# BlueDaq_V1_0.net
KiCad netlist of a schematic drawn in EAGLE
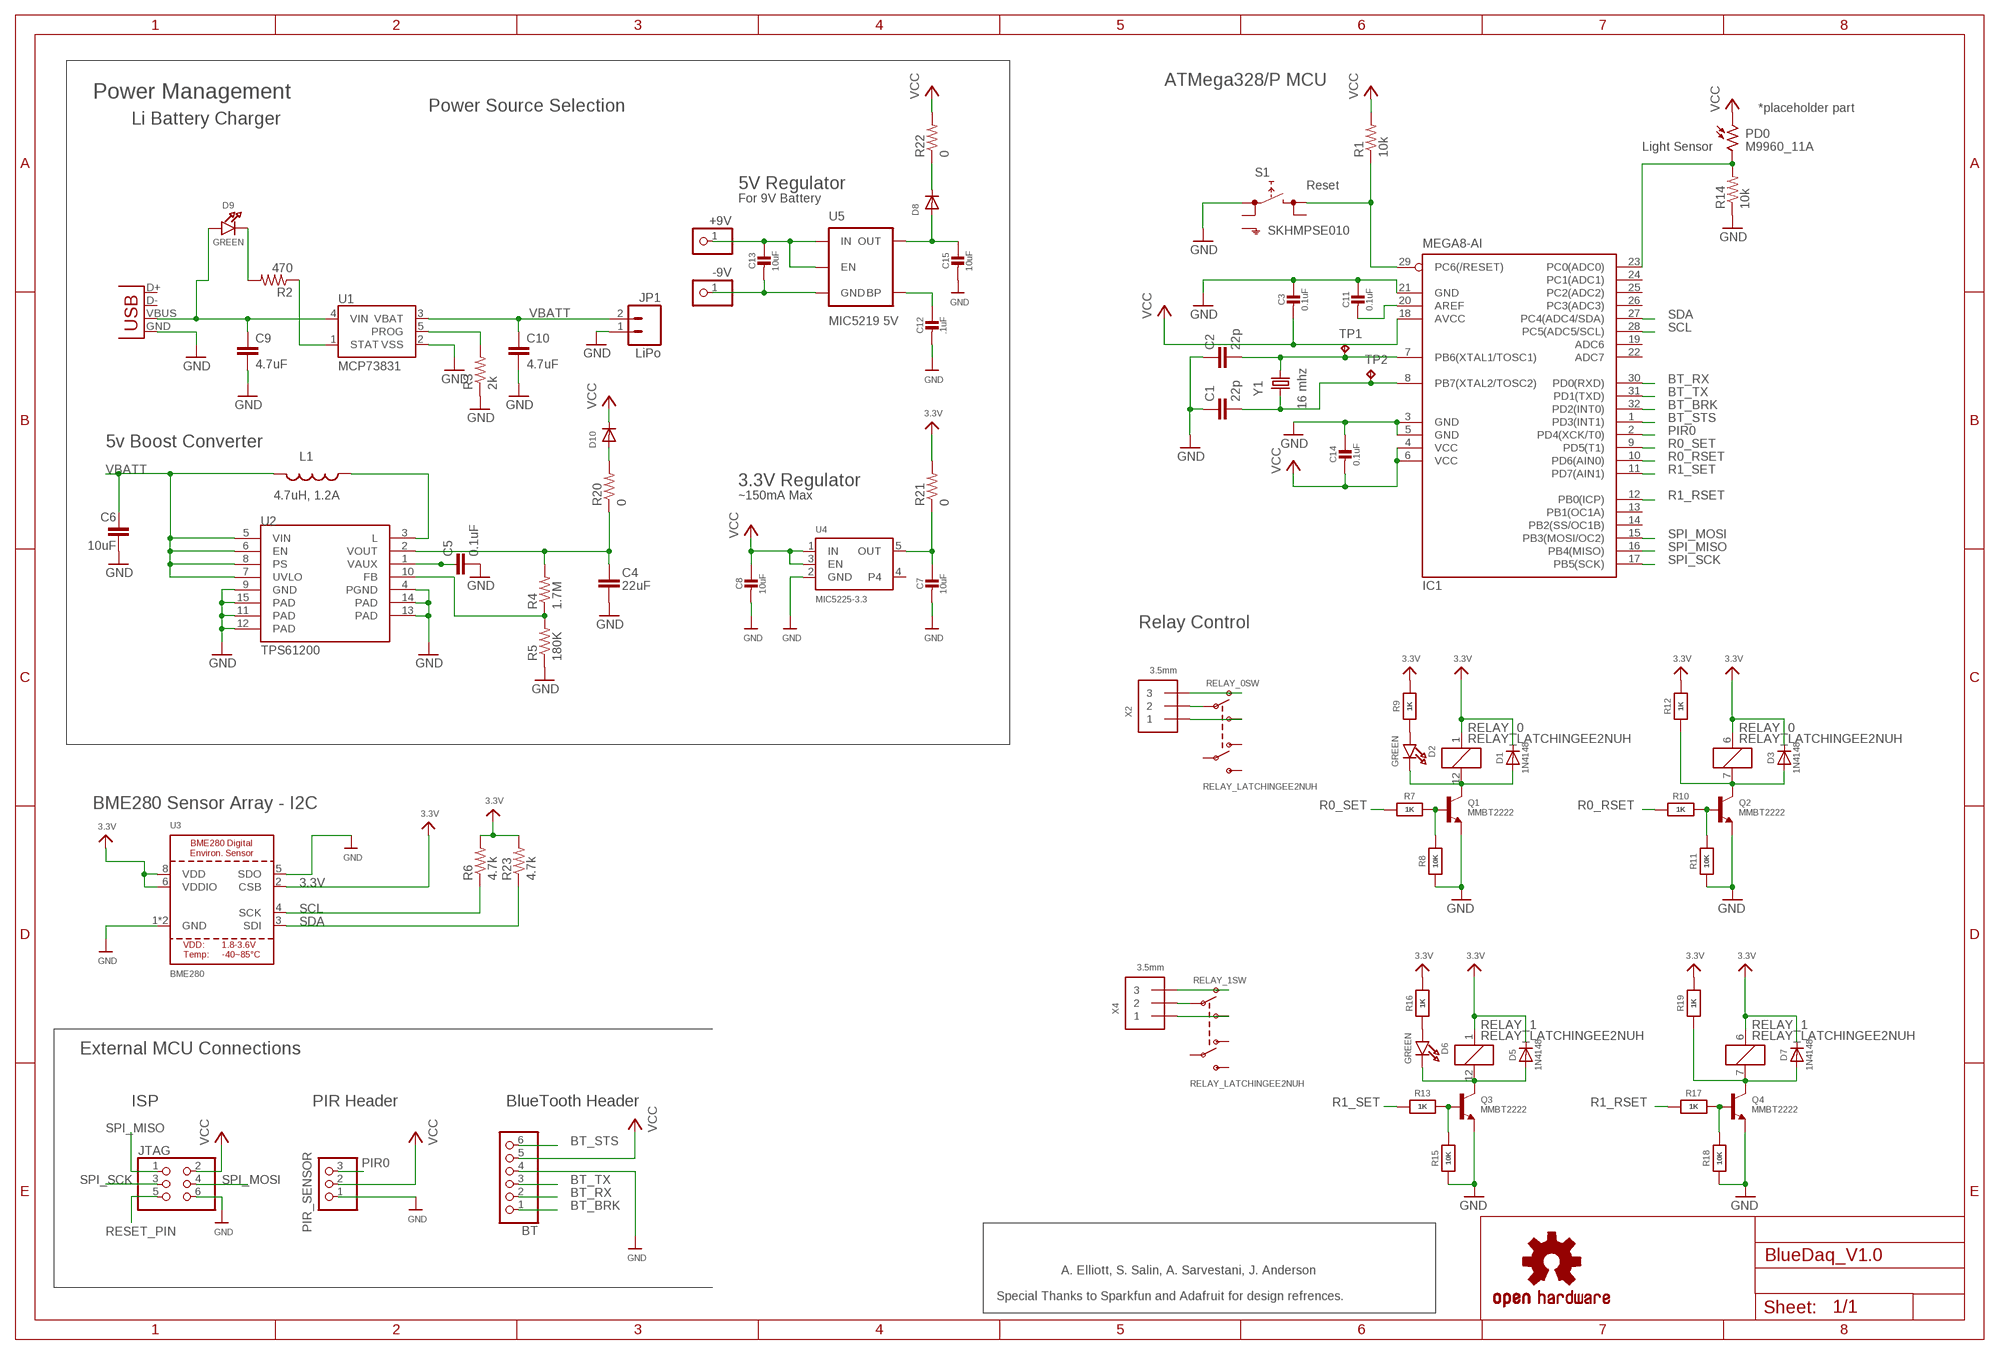
[diagram p0: schematic, sheet 1]

(export (version "E")
  (design (tool "Eeschema 10.0.6"))
  (components
    (comp (ref "+9V")
      (value "PINHD-1X1")
      (footprint "eagle-import:1X01")
      (libsource (lib "eagle-import") (part "PINHD-1X1"))
    )
    (comp (ref "-9V")
      (value "PINHD-1X1")
      (footprint "eagle-import:1X01")
      (libsource (lib "eagle-import") (part "PINHD-1X1"))
    )
    (comp (ref "BT")
      (value "PINHD-1X6")
      (footprint "eagle-import:1X06")
      (libsource (lib "eagle-import") (part "PINHD-1X6"))
    )
    (comp (ref "C1")
      (value "22p")
      (footprint "eagle-import:C0805")
      (libsource (lib "eagle-import") (part "C-EUC0805"))
    )
    (comp (ref "C2")
      (value "22p")
      (footprint "eagle-import:C0805")
      (libsource (lib "eagle-import") (part "C-EUC0805"))
    )
    (comp (ref "C3")
      (value "0.1uF")
      (footprint "eagle-import:0805-NO@1")
      (libsource (lib "eagle-import") (part "CAP_CERAMIC0805-NOOUTLINE"))
    )
    (comp (ref "C4")
      (value "22uF")
      (footprint "eagle-import:0805")
      (libsource (lib "eagle-import") (part "CAP0805"))
    )
    (comp (ref "C5")
      (value "0.1uF")
      (footprint "eagle-import:0805")
      (libsource (lib "eagle-import") (part "SparkFun_CAP0805"))
    )
    (comp (ref "C6")
      (value "10uF")
      (footprint "eagle-import:1206")
      (libsource (lib "eagle-import") (part "CAP1206"))
    )
    (comp (ref "C7")
      (value "10uF")
      (footprint "eagle-import:0805-NO@1")
      (libsource (lib "eagle-import") (part "CAP_CERAMIC0805-NOOUTLINE"))
    )
    (comp (ref "C8")
      (value "10uF")
      (footprint "eagle-import:0805-NO@1")
      (libsource (lib "eagle-import") (part "CAP_CERAMIC0805-NOOUTLINE"))
    )
    (comp (ref "C9")
      (value "4.7uF")
      (footprint "eagle-import:0805")
      (libsource (lib "eagle-import") (part "SparkFun_CAP0805"))
    )
    (comp (ref "C10")
      (value "4.7uF")
      (footprint "eagle-import:0805")
      (libsource (lib "eagle-import") (part "SparkFun_CAP0805"))
    )
    (comp (ref "C11")
      (value "0.1uF")
      (footprint "eagle-import:0805-NO@1")
      (libsource (lib "eagle-import") (part "CAP_CERAMIC0805-NOOUTLINE"))
    )
    (comp (ref "C12")
      (value ".1uF")
      (footprint "eagle-import:0805-NO@1")
      (libsource (lib "eagle-import") (part "CAP_CERAMIC0805-NOOUTLINE"))
    )
    (comp (ref "C13")
      (value "10uF")
      (footprint "eagle-import:0805-NO@1")
      (libsource (lib "eagle-import") (part "CAP_CERAMIC0805-NOOUTLINE"))
    )
    (comp (ref "C14")
      (value "0.1uF")
      (footprint "eagle-import:0805-NO@1")
      (libsource (lib "eagle-import") (part "CAP_CERAMIC0805-NOOUTLINE"))
    )
    (comp (ref "C15")
      (value "10uF")
      (footprint "eagle-import:0805-NO@1")
      (libsource (lib "eagle-import") (part "CAP_CERAMIC0805-NOOUTLINE"))
    )
    (comp (ref "D1")
      (value "1N4148")
      (footprint "eagle-import:SOD-323")
      (libsource (lib "eagle-import") (part "DIODESOD-323"))
    )
    (comp (ref "D2")
      (value "GREEN")
      (footprint "eagle-import:CHIPLED_0805_NOOUTLINE")
      (libsource (lib "eagle-import") (part "LED0805_NOOUTLINE"))
    )
    (comp (ref "D3")
      (value "1N4148")
      (footprint "eagle-import:SOD-323")
      (libsource (lib "eagle-import") (part "DIODESOD-323"))
    )
    (comp (ref "D5")
      (value "1N4148")
      (footprint "eagle-import:SOD-323")
      (libsource (lib "eagle-import") (part "DIODESOD-323"))
    )
    (comp (ref "D6")
      (value "GREEN")
      (footprint "eagle-import:CHIPLED_0805_NOOUTLINE")
      (libsource (lib "eagle-import") (part "LED0805_NOOUTLINE"))
    )
    (comp (ref "D7")
      (value "1N4148")
      (footprint "eagle-import:SOD-323")
      (libsource (lib "eagle-import") (part "DIODESOD-323"))
    )
    (comp (ref "D8")
      (value "DIODESMA")
      (footprint "eagle-import:SMADIODE")
      (libsource (lib "eagle-import") (part "DIODESMA"))
    )
    (comp (ref "D9")
      (value "GREEN")
      (footprint "eagle-import:CHIPLED_0805_NOOUTLINE")
      (libsource (lib "eagle-import") (part "LED0805_NOOUTLINE"))
    )
    (comp (ref "D10")
      (value "DIODESMA")
      (footprint "eagle-import:SMADIODE")
      (libsource (lib "eagle-import") (part "DIODESMA"))
    )
    (comp (ref "IC1")
      (value "MEGA8-AI")
      (footprint "eagle-import:TQFP32-08")
      (fields (field (name "MPN") "ATMEGA8-16AU"))
      (libsource (lib "eagle-import") (part "MEGA8-AI"))
    )
    (comp (ref "JP1")
      (value "LiPo")
      (footprint "eagle-import:JST-2-SMD")
      (libsource (lib "eagle-import") (part "M02-JST-2MM-SMT"))
    )
    (comp (ref "JTAG")
      (value "PINHD-2X3")
      (footprint "eagle-import:2X03")
      (libsource (lib "eagle-import") (part "PINHD-2X3"))
    )
    (comp (ref "L1")
      (value "4.7uH, 1.2A")
      (footprint "eagle-import:CDRH2D09")
      (libsource (lib "eagle-import") (part "INDUCTOR."))
    )
    (comp (ref "PD0")
      (value "M9960_11A")
      (footprint "eagle-import:M9960")
      (libsource (lib "eagle-import") (part "M9960_11A"))
    )
    (comp (ref "PIR_SENSOR")
      (value "PINHD-1X3")
      (footprint "eagle-import:1X03")
      (libsource (lib "eagle-import") (part "PINHD-1X3"))
    )
    (comp (ref "Q1")
      (value "MMBT2222")
      (footprint "eagle-import:SOT23-R")
      (libsource (lib "eagle-import") (part "TRANSISTOR_NPN"))
    )
    (comp (ref "Q2")
      (value "MMBT2222")
      (footprint "eagle-import:SOT23-R")
      (libsource (lib "eagle-import") (part "TRANSISTOR_NPN"))
    )
    (comp (ref "Q3")
      (value "MMBT2222")
      (footprint "eagle-import:SOT23-R")
      (libsource (lib "eagle-import") (part "TRANSISTOR_NPN"))
    )
    (comp (ref "Q4")
      (value "MMBT2222")
      (footprint "eagle-import:SOT23-R")
      (libsource (lib "eagle-import") (part "TRANSISTOR_NPN"))
    )
    (comp (ref "R1")
      (value "10k")
      (footprint "eagle-import:R0805")
      (libsource (lib "eagle-import") (part "R-US_R0805"))
    )
    (comp (ref "R2")
      (value "470")
      (footprint "eagle-import:R0805")
      (libsource (lib "eagle-import") (part "R-US_R0805"))
    )
    (comp (ref "R3")
      (value "2k")
      (footprint "eagle-import:R0805")
      (libsource (lib "eagle-import") (part "R-US_R0805"))
    )
    (comp (ref "R4")
      (value "1.7M")
      (footprint "eagle-import:R0805")
      (libsource (lib "eagle-import") (part "R-US_R0805"))
    )
    (comp (ref "R5")
      (value "180K")
      (footprint "eagle-import:R0805")
      (libsource (lib "eagle-import") (part "R-US_R0805"))
    )
    (comp (ref "R6")
      (value "4.7k")
      (footprint "eagle-import:R0805")
      (libsource (lib "eagle-import") (part "R-US_R0805"))
    )
    (comp (ref "R7")
      (value "1K")
      (footprint "eagle-import:0805-NO")
      (libsource (lib "eagle-import") (part "RESISTOR0805_NOOUTLINE"))
    )
    (comp (ref "R8")
      (value "10K")
      (footprint "eagle-import:0805-NO")
      (libsource (lib "eagle-import") (part "RESISTOR0805_NOOUTLINE"))
    )
    (comp (ref "R9")
      (value "1K")
      (footprint "eagle-import:0805-NO")
      (libsource (lib "eagle-import") (part "RESISTOR0805_NOOUTLINE"))
    )
    (comp (ref "R10")
      (value "1K")
      (footprint "eagle-import:0805-NO")
      (libsource (lib "eagle-import") (part "RESISTOR0805_NOOUTLINE"))
    )
    (comp (ref "R11")
      (value "10K")
      (footprint "eagle-import:0805-NO")
      (libsource (lib "eagle-import") (part "RESISTOR0805_NOOUTLINE"))
    )
    (comp (ref "R12")
      (value "1K")
      (footprint "eagle-import:0805-NO")
      (libsource (lib "eagle-import") (part "RESISTOR0805_NOOUTLINE"))
    )
    (comp (ref "R13")
      (value "1K")
      (footprint "eagle-import:0805-NO")
      (libsource (lib "eagle-import") (part "RESISTOR0805_NOOUTLINE"))
    )
    (comp (ref "R14")
      (value "10k")
      (footprint "eagle-import:R0805")
      (libsource (lib "eagle-import") (part "R-US_R0805"))
    )
    (comp (ref "R15")
      (value "10K")
      (footprint "eagle-import:0805-NO")
      (libsource (lib "eagle-import") (part "RESISTOR0805_NOOUTLINE"))
    )
    (comp (ref "R16")
      (value "1K")
      (footprint "eagle-import:0805-NO")
      (libsource (lib "eagle-import") (part "RESISTOR0805_NOOUTLINE"))
    )
    (comp (ref "R17")
      (value "1K")
      (footprint "eagle-import:0805-NO")
      (libsource (lib "eagle-import") (part "RESISTOR0805_NOOUTLINE"))
    )
    (comp (ref "R18")
      (value "10K")
      (footprint "eagle-import:0805-NO")
      (libsource (lib "eagle-import") (part "RESISTOR0805_NOOUTLINE"))
    )
    (comp (ref "R19")
      (value "1K")
      (footprint "eagle-import:0805-NO")
      (libsource (lib "eagle-import") (part "RESISTOR0805_NOOUTLINE"))
    )
    (comp (ref "R20")
      (value "0")
      (footprint "eagle-import:R0805")
      (libsource (lib "eagle-import") (part "R-US_R0805"))
    )
    (comp (ref "R21")
      (value "0")
      (footprint "eagle-import:R0805")
      (libsource (lib "eagle-import") (part "R-US_R0805"))
    )
    (comp (ref "R22")
      (value "0")
      (footprint "eagle-import:R0805")
      (libsource (lib "eagle-import") (part "R-US_R0805"))
    )
    (comp (ref "R23")
      (value "4.7k")
      (footprint "eagle-import:R0805")
      (libsource (lib "eagle-import") (part "R-US_R0805"))
    )
    (comp (ref "RELAY_0")
      (value "RELAY_LATCHINGEE2NUH")
      (footprint "eagle-import:RELAY_EE2_LATCH")
      (libsource (lib "eagle-import") (part "RELAY_LATCHINGEE2NUH"))
    )
    (comp (ref "RELAY_1")
      (value "RELAY_LATCHINGEE2NUH")
      (footprint "eagle-import:RELAY_EE2_LATCH")
      (libsource (lib "eagle-import") (part "RELAY_LATCHINGEE2NUH"))
    )
    (comp (ref "S1")
      (value "SKHMPSE010")
      (footprint "eagle-import:SKHMPXE010")
      (libsource (lib "eagle-import") (part "SKHMPE010S"))
    )
    (comp (ref "TP1")
      (value "TPTP19SQ")
      (footprint "eagle-import:TP19SQ")
      (libsource (lib "eagle-import") (part "TPTP19SQ"))
    )
    (comp (ref "TP2")
      (value "TPTP19SQ")
      (footprint "eagle-import:TP19SQ")
      (libsource (lib "eagle-import") (part "TPTP19SQ"))
    )
    (comp (ref "U$22")
      (value "OSHW-LOGOS")
      (footprint "eagle-import:OSHW-LOGO-S")
      (libsource (lib "eagle-import") (part "OSHW-LOGOS"))
    )
    (comp (ref "U1")
      (value "MCP73831")
      (footprint "eagle-import:SOT23-5")
      (libsource (lib "eagle-import") (part "MCP73831"))
    )
    (comp (ref "U2")
      (value "TPS61200")
      (footprint "eagle-import:QFN-10_PAD")
      (libsource (lib "eagle-import") (part "TPS61200"))
    )
    (comp (ref "U3")
      (value "BME280")
      (footprint "eagle-import:BME280")
      (libsource (lib "eagle-import") (part "BME280"))
    )
    (comp (ref "U4")
      (value "MIC5225-3.3")
      (footprint "eagle-import:SOT23-5")
      (libsource (lib "eagle-import") (part "VREG_SOT23-5"))
    )
    (comp (ref "U5")
      (value "MIC5219 5V")
      (footprint "eagle-import:SOT23-5")
      (libsource (lib "eagle-import") (part "V_REG_MIC52195V"))
    )
    (comp (ref "X1")
      (value "USB-MICROB")
      (footprint "eagle-import:USB-MICROB")
      (libsource (lib "eagle-import") (part "USB-MICROB"))
    )
    (comp (ref "X2")
      (value "3.5mm")
      (footprint "eagle-import:TERMBLOCK_1X3-3.5MM")
      (libsource (lib "eagle-import") (part "TERMBLOCK_1X3"))
    )
    (comp (ref "X4")
      (value "3.5mm")
      (footprint "eagle-import:TERMBLOCK_1X3-3.5MM")
      (libsource (lib "eagle-import") (part "TERMBLOCK_1X3"))
    )
    (comp (ref "Y1")
      (value "16 mhz")
      (footprint "eagle-import:HC49U-V")
      (libsource (lib "eagle-import") (part "CRYSTALHC49UV"))
    )
  )
  (nets
    (net (code "1") (name "/BT_BRK") (class "Default")
      (node (ref "BT") (pin "1") (pinfunction "1_1") (pintype "passive"))
      (node (ref "IC1") (pin "32") (pinfunction "PD2(INT0)_32") (pintype "bidirectional"))
    )
    (net (code "2") (name "/BT_RX") (class "Default")
      (node (ref "BT") (pin "2") (pinfunction "2_2") (pintype "passive"))
      (node (ref "IC1") (pin "30") (pinfunction "PD0(RXD)_30") (pintype "bidirectional"))
    )
    (net (code "3") (name "/BT_STS") (class "Default")
      (node (ref "BT") (pin "6") (pinfunction "6_6") (pintype "passive"))
      (node (ref "IC1") (pin "1") (pinfunction "PD3(INT1)_1") (pintype "bidirectional"))
    )
    (net (code "4") (name "/BT_TX") (class "Default")
      (node (ref "BT") (pin "3") (pinfunction "3_3") (pintype "passive"))
      (node (ref "IC1") (pin "31") (pinfunction "PD1(TXD)_31") (pintype "bidirectional"))
    )
    (net (code "5") (name "/PIR0") (class "Default")
      (node (ref "IC1") (pin "2") (pinfunction "PD4(XCK/T0)_2") (pintype "bidirectional"))
      (node (ref "PIR_SENSOR") (pin "3") (pinfunction "3_3") (pintype "passive"))
    )
    (net (code "6") (name "/R0_RSET") (class "Default")
      (node (ref "IC1") (pin "10") (pinfunction "PD6(AIN0)_10") (pintype "bidirectional"))
      (node (ref "R10") (pin "1") (pinfunction "1_1") (pintype "passive"))
    )
    (net (code "7") (name "/R0_SET") (class "Default")
      (node (ref "IC1") (pin "9") (pinfunction "PD5(T1)_9") (pintype "bidirectional"))
      (node (ref "R7") (pin "1") (pinfunction "1_1") (pintype "passive"))
    )
    (net (code "8") (name "/R1_RSET") (class "Default")
      (node (ref "IC1") (pin "12") (pinfunction "PB0(ICP)_12") (pintype "bidirectional"))
      (node (ref "R17") (pin "1") (pinfunction "1_1") (pintype "passive"))
    )
    (net (code "9") (name "/R1_SET") (class "Default")
      (node (ref "IC1") (pin "11") (pinfunction "PD7(AIN1)_11") (pintype "bidirectional"))
      (node (ref "R13") (pin "1") (pinfunction "1_1") (pintype "passive"))
    )
    (net (code "10") (name "/RESET_PIN") (class "Default")
      (node (ref "IC1") (pin "29") (pinfunction "PC6(/RESET)_29") (pintype "bidirectional"))
      (node (ref "JTAG") (pin "5") (pinfunction "5_5") (pintype "passive"))
      (node (ref "R1") (pin "1") (pinfunction "1_1") (pintype "passive"))
      (node (ref "S1") (pin "3") (pinfunction "2.1_3") (pintype "passive"))
    )
    (net (code "11") (name "/SCL") (class "Default")
      (node (ref "IC1") (pin "28") (pinfunction "PC5(ADC5/SCL)_28") (pintype "bidirectional"))
      (node (ref "R6") (pin "1") (pinfunction "1_1") (pintype "passive"))
      (node (ref "U3") (pin "4") (pinfunction "SCK_4") (pintype "input"))
    )
    (net (code "12") (name "/SDA") (class "Default")
      (node (ref "IC1") (pin "27") (pinfunction "PC4(ADC4/SDA)_27") (pintype "bidirectional"))
      (node (ref "R23") (pin "1") (pinfunction "1_1") (pintype "passive"))
      (node (ref "U3") (pin "3") (pinfunction "SDI_3") (pintype "input"))
    )
    (net (code "13") (name "/SPI_MISO") (class "Default")
      (node (ref "IC1") (pin "16") (pinfunction "PB4(MISO)_16") (pintype "bidirectional"))
      (node (ref "JTAG") (pin "1") (pinfunction "1_1") (pintype "passive"))
    )
    (net (code "14") (name "/SPI_MOSI") (class "Default")
      (node (ref "IC1") (pin "15") (pinfunction "PB3(MOSI/OC2)_15") (pintype "bidirectional"))
      (node (ref "JTAG") (pin "4") (pinfunction "4_4") (pintype "passive"))
    )
    (net (code "15") (name "/SPI_SCK") (class "Default")
      (node (ref "IC1") (pin "17") (pinfunction "PB5(SCK)_17") (pintype "bidirectional"))
      (node (ref "JTAG") (pin "3") (pinfunction "3_3") (pintype "passive"))
    )
    (net (code "16") (name "/VBATT") (class "Default")
      (node (ref "C10") (pin "1") (pinfunction "1_1") (pintype "passive"))
      (node (ref "C6") (pin "1") (pinfunction "1_1") (pintype "passive"))
      (node (ref "JP1") (pin "2") (pinfunction "2_2") (pintype "passive"))
      (node (ref "L1") (pin "P$2") (pinfunction "2_P$2") (pintype "passive"))
      (node (ref "U1") (pin "3") (pinfunction "VBAT_3") (pintype "power_in"))
      (node (ref "U2") (pin "5") (pinfunction "VIN_5") (pintype "power_in"))
      (node (ref "U2") (pin "6") (pinfunction "EN_6") (pintype "input"))
      (node (ref "U2") (pin "7") (pinfunction "UVLO_7") (pintype "passive"))
      (node (ref "U2") (pin "8") (pinfunction "PS_8") (pintype "input"))
    )
    (net (code "17") (name "3.3V") (class "Default")
      (node (ref "D1") (pin "C") (pinfunction "C_C") (pintype "passive"))
      (node (ref "D3") (pin "C") (pinfunction "C_C") (pintype "passive"))
      (node (ref "D5") (pin "C") (pinfunction "C_C") (pintype "passive"))
      (node (ref "D7") (pin "C") (pinfunction "C_C") (pintype "passive"))
      (node (ref "R12") (pin "2") (pinfunction "2_2") (pintype "passive"))
      (node (ref "R16") (pin "2") (pinfunction "2_2") (pintype "passive"))
      (node (ref "R19") (pin "2") (pinfunction "2_2") (pintype "passive"))
      (node (ref "R21") (pin "2") (pinfunction "2_2") (pintype "passive"))
      (node (ref "R23") (pin "2") (pinfunction "2_2") (pintype "passive"))
      (node (ref "R6") (pin "2") (pinfunction "2_2") (pintype "passive"))
      (node (ref "R9") (pin "2") (pinfunction "2_2") (pintype "passive"))
      (node (ref "RELAY_0") (pin "1") (pinfunction "1_1") (pintype "passive"))
      (node (ref "RELAY_0") (pin "6") (pinfunction "1_6") (pintype "passive"))
      (node (ref "RELAY_1") (pin "1") (pinfunction "1_1") (pintype "passive"))
      (node (ref "RELAY_1") (pin "6") (pinfunction "1_6") (pintype "passive"))
      (node (ref "U3") (pin "2") (pinfunction "CSB_2") (pintype "input"))
      (node (ref "U3") (pin "6") (pinfunction "VDDIO_6") (pintype "power_in"))
      (node (ref "U3") (pin "8") (pinfunction "VDD_8") (pintype "power_in"))
    )
    (net (code "18") (name "GND") (class "Default")
      (node (ref "BT") (pin "4") (pinfunction "4_4") (pintype "passive"))
      (node (ref "C1") (pin "1") (pinfunction "1_1") (pintype "passive"))
      (node (ref "C10") (pin "2") (pinfunction "2_2") (pintype "passive"))
      (node (ref "C11") (pin "1") (pinfunction "1_1") (pintype "passive"))
      (node (ref "C12") (pin "2") (pinfunction "2_2") (pintype "passive"))
      (node (ref "C14") (pin "1") (pinfunction "1_1") (pintype "passive"))
      (node (ref "C15") (pin "2") (pinfunction "2_2") (pintype "passive"))
      (node (ref "C2") (pin "1") (pinfunction "1_1") (pintype "passive"))
      (node (ref "C3") (pin "1") (pinfunction "1_1") (pintype "passive"))
      (node (ref "C4") (pin "2") (pinfunction "2_2") (pintype "passive"))
      (node (ref "C5") (pin "2") (pinfunction "2_2") (pintype "passive"))
      (node (ref "C6") (pin "2") (pinfunction "2_2") (pintype "passive"))
      (node (ref "C7") (pin "2") (pinfunction "2_2") (pintype "passive"))
      (node (ref "C8") (pin "2") (pinfunction "2_2") (pintype "passive"))
      (node (ref "C9") (pin "2") (pinfunction "2_2") (pintype "passive"))
      (node (ref "IC1") (pin "21") (pinfunction "GND_21") (pintype "power_in"))
      (node (ref "IC1") (pin "3") (pinfunction "GND_3") (pintype "power_in"))
      (node (ref "IC1") (pin "5") (pinfunction "GND_5") (pintype "power_in"))
      (node (ref "JP1") (pin "1") (pinfunction "1_1") (pintype "passive"))
      (node (ref "JTAG") (pin "6") (pinfunction "6_6") (pintype "passive"))
      (node (ref "PIR_SENSOR") (pin "1") (pinfunction "1_1") (pintype "passive"))
      (node (ref "Q1") (pin "2") (pinfunction "E_2") (pintype "passive"))
      (node (ref "Q2") (pin "2") (pinfunction "E_2") (pintype "passive"))
      (node (ref "Q3") (pin "2") (pinfunction "E_2") (pintype "passive"))
      (node (ref "Q4") (pin "2") (pinfunction "E_2") (pintype "passive"))
      (node (ref "R11") (pin "1") (pinfunction "1_1") (pintype "passive"))
      (node (ref "R14") (pin "1") (pinfunction "1_1") (pintype "passive"))
      (node (ref "R15") (pin "1") (pinfunction "1_1") (pintype "passive"))
      (node (ref "R18") (pin "1") (pinfunction "1_1") (pintype "passive"))
      (node (ref "R3") (pin "1") (pinfunction "1_1") (pintype "passive"))
      (node (ref "R5") (pin "1") (pinfunction "1_1") (pintype "passive"))
      (node (ref "R8") (pin "1") (pinfunction "1_1") (pintype "passive"))
      (node (ref "S1") (pin "1") (pinfunction "1.1_1") (pintype "passive"))
      (node (ref "U1") (pin "2") (pinfunction "VSS_2") (pintype "power_in"))
      (node (ref "U2") (pin "11") (pinfunction "PAD_11") (pintype "power_in"))
      (node (ref "U2") (pin "12") (pinfunction "PAD_12") (pintype "power_in"))
      (node (ref "U2") (pin "13") (pinfunction "PAD_13") (pintype "power_in"))
      (node (ref "U2") (pin "14") (pinfunction "PAD_14") (pintype "power_in"))
      (node (ref "U2") (pin "15") (pinfunction "PAD_15") (pintype "power_in"))
      (node (ref "U2") (pin "4") (pinfunction "PGND_4") (pintype "power_in"))
      (node (ref "U2") (pin "9") (pinfunction "GND_9") (pintype "power_in"))
      (node (ref "U3") (pin "1") (pinfunction "GND_1") (pintype "power_in"))
      (node (ref "U3") (pin "5") (pinfunction "SDO_5") (pintype "output"))
      (node (ref "U3") (pin "7") (pinfunction "GND_7") (pintype "power_in"))
      (node (ref "U4") (pin "2") (pinfunction "GND_2") (pintype "power_in"))
      (node (ref "X1") (pin "GND") (pinfunction "GND_GND") (pintype "bidirectional"))
    )
    (net (code "19") (name "Net-(D2-PadA)") (class "Default")
      (node (ref "D2") (pin "A") (pinfunction "A_A") (pintype "passive"))
      (node (ref "R9") (pin "1") (pinfunction "1_1") (pintype "passive"))
    )
    (net (code "20") (name "Net-(D6-PadA)") (class "Default")
      (node (ref "D6") (pin "A") (pinfunction "A_A") (pintype "passive"))
      (node (ref "R16") (pin "1") (pinfunction "1_1") (pintype "passive"))
    )
    (net (code "21") (name "Net-(D8-PadC)") (class "Default")
      (node (ref "D8") (pin "C") (pinfunction "C_C") (pintype "passive"))
      (node (ref "R22") (pin "1") (pinfunction "1_1") (pintype "passive"))
    )
    (net (code "22") (name "Net-(D9-PadC)") (class "Default")
      (node (ref "D9") (pin "C") (pinfunction "C_C") (pintype "passive"))
      (node (ref "R2") (pin "2") (pinfunction "2_2") (pintype "passive"))
    )
    (net (code "23") (name "Net-(D10-PadA)") (class "Default")
      (node (ref "D10") (pin "A") (pinfunction "A_A") (pintype "passive"))
      (node (ref "R20") (pin "2") (pinfunction "2_2") (pintype "passive"))
    )
    (net (code "24") (name "Net-(IC1-AREF)") (class "Default")
      (node (ref "C11") (pin "2") (pinfunction "2_2") (pintype "passive"))
      (node (ref "IC1") (pin "20") (pinfunction "AREF_20") (pintype "passive"))
    )
    (net (code "25") (name "Net-(IC1-PB6(XTAL1{slash}TOSC1))") (class "Default")
      (node (ref "C2") (pin "2") (pinfunction "2_2") (pintype "passive"))
      (node (ref "IC1") (pin "7") (pinfunction "PB6(XTAL1/TOSC1)_7") (pintype "bidirectional"))
      (node (ref "TP1") (pin "TP") (pinfunction "TP_TP") (pintype "input"))
      (node (ref "Y1") (pin "2") (pinfunction "2_2") (pintype "passive"))
    )
    (net (code "26") (name "Net-(IC1-PB7(XTAL2{slash}TOSC2))") (class "Default")
      (node (ref "C1") (pin "2") (pinfunction "2_2") (pintype "passive"))
      (node (ref "IC1") (pin "8") (pinfunction "PB7(XTAL2/TOSC2)_8") (pintype "bidirectional"))
      (node (ref "TP2") (pin "TP") (pinfunction "TP_TP") (pintype "input"))
      (node (ref "Y1") (pin "1") (pinfunction "1_1") (pintype "passive"))
    )
    (net (code "27") (name "Net-(IC1-PC0(ADC0))") (class "Default")
      (node (ref "IC1") (pin "23") (pinfunction "PC0(ADC0)_23") (pintype "bidirectional"))
      (node (ref "PD0") (pin "2") (pinfunction "2_2") (pintype "passive"))
      (node (ref "R14") (pin "2") (pinfunction "2_2") (pintype "passive"))
    )
    (net (code "28") (name "Net-(L1-1)") (class "Default")
      (node (ref "L1") (pin "P$1") (pinfunction "1_P$1") (pintype "passive"))
      (node (ref "U2") (pin "3") (pinfunction "L_3") (pintype "passive"))
    )
    (net (code "29") (name "Net-(Q1-B)") (class "Default")
      (node (ref "Q1") (pin "1") (pinfunction "B_1") (pintype "passive"))
      (node (ref "R7") (pin "2") (pinfunction "2_2") (pintype "passive"))
      (node (ref "R8") (pin "2") (pinfunction "2_2") (pintype "passive"))
    )
    (net (code "30") (name "Net-(Q1-C)") (class "Default")
      (node (ref "D1") (pin "A") (pinfunction "A_A") (pintype "passive"))
      (node (ref "D2") (pin "C") (pinfunction "C_C") (pintype "passive"))
      (node (ref "Q1") (pin "3") (pinfunction "C_3") (pintype "passive"))
      (node (ref "RELAY_0") (pin "12") (pinfunction "2_12") (pintype "passive"))
    )
    (net (code "31") (name "Net-(Q2-B)") (class "Default")
      (node (ref "Q2") (pin "1") (pinfunction "B_1") (pintype "passive"))
      (node (ref "R10") (pin "2") (pinfunction "2_2") (pintype "passive"))
      (node (ref "R11") (pin "2") (pinfunction "2_2") (pintype "passive"))
    )
    (net (code "32") (name "Net-(Q2-C)") (class "Default")
      (node (ref "D3") (pin "A") (pinfunction "A_A") (pintype "passive"))
      (node (ref "Q2") (pin "3") (pinfunction "C_3") (pintype "passive"))
      (node (ref "R12") (pin "1") (pinfunction "1_1") (pintype "passive"))
      (node (ref "RELAY_0") (pin "7") (pinfunction "2_7") (pintype "passive"))
    )
    (net (code "33") (name "Net-(Q3-B)") (class "Default")
      (node (ref "Q3") (pin "1") (pinfunction "B_1") (pintype "passive"))
      (node (ref "R13") (pin "2") (pinfunction "2_2") (pintype "passive"))
      (node (ref "R15") (pin "2") (pinfunction "2_2") (pintype "passive"))
    )
    (net (code "34") (name "Net-(Q3-C)") (class "Default")
      (node (ref "D5") (pin "A") (pinfunction "A_A") (pintype "passive"))
      (node (ref "D6") (pin "C") (pinfunction "C_C") (pintype "passive"))
      (node (ref "Q3") (pin "3") (pinfunction "C_3") (pintype "passive"))
      (node (ref "RELAY_1") (pin "12") (pinfunction "2_12") (pintype "passive"))
    )
    (net (code "35") (name "Net-(Q4-B)") (class "Default")
      (node (ref "Q4") (pin "1") (pinfunction "B_1") (pintype "passive"))
      (node (ref "R17") (pin "2") (pinfunction "2_2") (pintype "passive"))
      (node (ref "R18") (pin "2") (pinfunction "2_2") (pintype "passive"))
    )
    (net (code "36") (name "Net-(Q4-C)") (class "Default")
      (node (ref "D7") (pin "A") (pinfunction "A_A") (pintype "passive"))
      (node (ref "Q4") (pin "3") (pinfunction "C_3") (pintype "passive"))
      (node (ref "R19") (pin "1") (pinfunction "1_1") (pintype "passive"))
      (node (ref "RELAY_1") (pin "7") (pinfunction "2_7") (pintype "passive"))
    )
    (net (code "37") (name "Net-(RELAY_0C-O1)") (class "Default")
      (node (ref "RELAY_0") (pin "10") (pinfunction "O1_10") (pintype "passive"))
      (node (ref "X2") (pin "3") (pinfunction "3_3") (pintype "passive"))
    )
    (net (code "38") (name "Net-(RELAY_0C-P1)") (class "Default")
      (node (ref "RELAY_0") (pin "9") (pinfunction "P1_9") (pintype "passive"))
      (node (ref "X2") (pin "2") (pinfunction "2_2") (pintype "passive"))
    )
    (net (code "39") (name "Net-(RELAY_0C-S1)") (class "Default")
      (node (ref "RELAY_0") (pin "8") (pinfunction "S1_8") (pintype "passive"))
      (node (ref "X2") (pin "1") (pinfunction "1_1") (pintype "passive"))
    )
    (net (code "40") (name "Net-(RELAY_1C-O1)") (class "Default")
      (node (ref "RELAY_1") (pin "10") (pinfunction "O1_10") (pintype "passive"))
      (node (ref "X4") (pin "3") (pinfunction "3_3") (pintype "passive"))
    )
    (net (code "41") (name "Net-(RELAY_1C-P1)") (class "Default")
      (node (ref "RELAY_1") (pin "9") (pinfunction "P1_9") (pintype "passive"))
      (node (ref "X4") (pin "2") (pinfunction "2_2") (pintype "passive"))
    )
    (net (code "42") (name "Net-(RELAY_1C-S1)") (class "Default")
      (node (ref "RELAY_1") (pin "8") (pinfunction "S1_8") (pintype "passive"))
      (node (ref "X4") (pin "1") (pinfunction "1_1") (pintype "passive"))
    )
    (net (code "43") (name "Net-(U1-PROG)") (class "Default")
      (node (ref "R3") (pin "2") (pinfunction "2_2") (pintype "passive"))
      (node (ref "U1") (pin "5") (pinfunction "PROG_5") (pintype "input"))
    )
    (net (code "44") (name "Net-(U1-STAT)") (class "Default")
      (node (ref "R2") (pin "1") (pinfunction "1_1") (pintype "passive"))
      (node (ref "U1") (pin "1") (pinfunction "STAT_1") (pintype "output"))
    )
    (net (code "45") (name "Net-(U1-VIN)") (class "Default")
      (node (ref "C9") (pin "1") (pinfunction "1_1") (pintype "passive"))
      (node (ref "D9") (pin "A") (pinfunction "A_A") (pintype "passive"))
      (node (ref "U1") (pin "4") (pinfunction "VIN_4") (pintype "power_in"))
      (node (ref "X1") (pin "VBUS") (pinfunction "VBUS_VBUS") (pintype "bidirectional"))
    )
    (net (code "46") (name "Net-(U2-FB)") (class "Default")
      (node (ref "R4") (pin "1") (pinfunction "1_1") (pintype "passive"))
      (node (ref "R5") (pin "2") (pinfunction "2_2") (pintype "passive"))
      (node (ref "U2") (pin "10") (pinfunction "FB_10") (pintype "passive"))
    )
    (net (code "47") (name "Net-(U2-VAUX)") (class "Default")
      (node (ref "C5") (pin "1") (pinfunction "1_1") (pintype "passive"))
      (node (ref "U2") (pin "1") (pinfunction "VAUX_1") (pintype "passive"))
    )
    (net (code "48") (name "Net-(U2-VOUT)") (class "Default")
      (node (ref "C4") (pin "1") (pinfunction "1_1") (pintype "passive"))
      (node (ref "R20") (pin "1") (pinfunction "1_1") (pintype "passive"))
      (node (ref "R4") (pin "2") (pinfunction "2_2") (pintype "passive"))
      (node (ref "U2") (pin "2") (pinfunction "VOUT_2") (pintype "passive"))
    )
    (net (code "49") (name "Net-(U4-OUT)") (class "Default")
      (node (ref "C7") (pin "1") (pinfunction "1_1") (pintype "passive"))
      (node (ref "R21") (pin "1") (pinfunction "1_1") (pintype "passive"))
      (node (ref "U4") (pin "5") (pinfunction "OUT_5") (pintype "power_in"))
    )
    (net (code "50") (name "Net-(U5-BP)") (class "Default")
      (node (ref "C12") (pin "1") (pinfunction "1_1") (pintype "passive"))
      (node (ref "U5") (pin "4") (pinfunction "BP_4") (pintype "input"))
    )
    (net (code "51") (name "Net-(U5-EN)") (class "Default")
      (node (ref "+9V") (pin "1") (pinfunction "1_1") (pintype "passive"))
      (node (ref "C13") (pin "1") (pinfunction "1_1") (pintype "passive"))
      (node (ref "U5") (pin "1") (pinfunction "IN_1") (pintype "input"))
      (node (ref "U5") (pin "3") (pinfunction "EN_3") (pintype "input"))
    )
    (net (code "52") (name "Net-(U5-GND)") (class "Default")
      (node (ref "-9V") (pin "1") (pinfunction "1_1") (pintype "passive"))
      (node (ref "C13") (pin "2") (pinfunction "2_2") (pintype "passive"))
      (node (ref "U5") (pin "2") (pinfunction "GND_2") (pintype "input"))
    )
    (net (code "53") (name "Net-(U5-OUT)") (class "Default")
      (node (ref "C15") (pin "1") (pinfunction "1_1") (pintype "passive"))
      (node (ref "D8") (pin "A") (pinfunction "A_A") (pintype "passive"))
      (node (ref "U5") (pin "5") (pinfunction "OUT_5") (pintype "passive"))
    )
    (net (code "54") (name "VCC") (class "Default")
      (node (ref "BT") (pin "5") (pinfunction "5_5") (pintype "passive"))
      (node (ref "C14") (pin "2") (pinfunction "2_2") (pintype "passive"))
      (node (ref "C3") (pin "2") (pinfunction "2_2") (pintype "passive"))
      (node (ref "C8") (pin "1") (pinfunction "1_1") (pintype "passive"))
      (node (ref "D10") (pin "C") (pinfunction "C_C") (pintype "passive"))
      (node (ref "IC1") (pin "18") (pinfunction "AVCC_18") (pintype "power_in"))
      (node (ref "IC1") (pin "4") (pinfunction "VCC_4") (pintype "power_in"))
      (node (ref "IC1") (pin "6") (pinfunction "VCC_6") (pintype "power_in"))
      (node (ref "JTAG") (pin "2") (pinfunction "2_2") (pintype "passive"))
      (node (ref "PD0") (pin "1") (pinfunction "1_1") (pintype "passive"))
      (node (ref "PIR_SENSOR") (pin "2") (pinfunction "2_2") (pintype "passive"))
      (node (ref "R1") (pin "2") (pinfunction "2_2") (pintype "passive"))
      (node (ref "R22") (pin "2") (pinfunction "2_2") (pintype "passive"))
      (node (ref "U4") (pin "1") (pinfunction "IN_1") (pintype "power_in"))
      (node (ref "U4") (pin "3") (pinfunction "EN_3") (pintype "input"))
    )
    (net (code "55") (name "unconnected-(IC1-ADC6-Pad19)") (class "Default")
      (node (ref "IC1") (pin "19") (pinfunction "ADC6_19") (pintype "bidirectional"))
    )
    (net (code "56") (name "unconnected-(IC1-ADC7-Pad22)") (class "Default")
      (node (ref "IC1") (pin "22") (pinfunction "ADC7_22") (pintype "bidirectional"))
    )
    (net (code "57") (name "unconnected-(IC1-PB1(OC1A)-Pad13)") (class "Default")
      (node (ref "IC1") (pin "13") (pinfunction "PB1(OC1A)_13") (pintype "bidirectional"))
    )
    (net (code "58") (name "unconnected-(IC1-PB2(SS{slash}OC1B)-Pad14)") (class "Default")
      (node (ref "IC1") (pin "14") (pinfunction "PB2(SS/OC1B)_14") (pintype "bidirectional"))
    )
    (net (code "59") (name "unconnected-(IC1-PC1(ADC1)-Pad24)") (class "Default")
      (node (ref "IC1") (pin "24") (pinfunction "PC1(ADC1)_24") (pintype "bidirectional"))
    )
    (net (code "60") (name "unconnected-(IC1-PC2(ADC2)-Pad25)") (class "Default")
      (node (ref "IC1") (pin "25") (pinfunction "PC2(ADC2)_25") (pintype "bidirectional"))
    )
    (net (code "61") (name "unconnected-(IC1-PC3(ADC3)-Pad26)") (class "Default")
      (node (ref "IC1") (pin "26") (pinfunction "PC3(ADC3)_26") (pintype "bidirectional"))
    )
    (net (code "62") (name "unconnected-(RELAY_0C-O2-Pad3)") (class "Default")
      (node (ref "RELAY_0") (pin "3") (pinfunction "O2_3") (pintype "passive"))
    )
    (net (code "63") (name "unconnected-(RELAY_0C-P2-Pad4)") (class "Default")
      (node (ref "RELAY_0") (pin "4") (pinfunction "P2_4") (pintype "passive"))
    )
    (net (code "64") (name "unconnected-(RELAY_0C-S2-Pad5)") (class "Default")
      (node (ref "RELAY_0") (pin "5") (pinfunction "S2_5") (pintype "passive"))
    )
    (net (code "65") (name "unconnected-(RELAY_1C-O2-Pad3)") (class "Default")
      (node (ref "RELAY_1") (pin "3") (pinfunction "O2_3") (pintype "passive"))
    )
    (net (code "66") (name "unconnected-(RELAY_1C-P2-Pad4)") (class "Default")
      (node (ref "RELAY_1") (pin "4") (pinfunction "P2_4") (pintype "passive"))
    )
    (net (code "67") (name "unconnected-(RELAY_1C-S2-Pad5)") (class "Default")
      (node (ref "RELAY_1") (pin "5") (pinfunction "S2_5") (pintype "passive"))
    )
    (net (code "68") (name "unconnected-(S1-1.2-Pad2)") (class "Default")
      (node (ref "S1") (pin "2") (pinfunction "1.2_2") (pintype "passive"))
    )
    (net (code "69") (name "unconnected-(S1-2.2-Pad4)") (class "Default")
      (node (ref "S1") (pin "4") (pinfunction "2.2_4") (pintype "passive"))
    )
    (net (code "70") (name "unconnected-(S1-SH-Pad5)") (class "Default")
      (node (ref "S1") (pin "5") (pinfunction "SH_5") (pintype "passive"))
    )
    (net (code "71") (name "unconnected-(U4-P4-Pad4)") (class "Default")
      (node (ref "U4") (pin "4") (pinfunction "P4_4") (pintype "bidirectional"))
    )
    (net (code "72") (name "unconnected-(X1-PadD+)") (class "Default")
      (node (ref "X1") (pin "D+") (pinfunction "D+_D+") (pintype "bidirectional"))
    )
    (net (code "73") (name "unconnected-(X1-PadD-)") (class "Default")
      (node (ref "X1") (pin "D-") (pinfunction "D-_D-") (pintype "bidirectional"))
    )
  )
)
